# usb_breakout.net
KiCad netlist of a schematic drawn in EAGLE
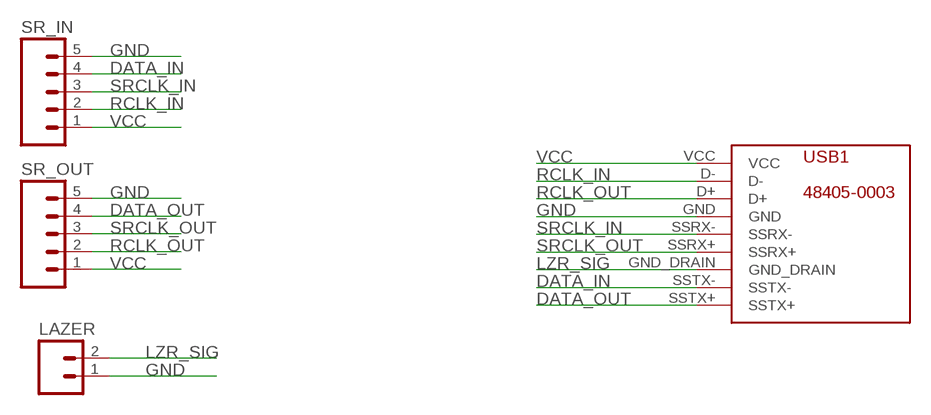
[diagram p0: schematic, sheet 1]

(export (version "E")
  (design (tool "Eeschema 10.0.6"))
  (components
    (comp (ref "LAZER")
      (value "M02PTH")
      (footprint "eagle-import:1X02")
      (libsource (lib "eagle-import") (part "M02PTH"))
    )
    (comp (ref "SR_IN")
      (value "M05PTH")
      (footprint "eagle-import:1X05")
      (libsource (lib "eagle-import") (part "M05PTH"))
    )
    (comp (ref "SR_OUT")
      (value "M05PTH")
      (footprint "eagle-import:1X05")
      (libsource (lib "eagle-import") (part "M05PTH"))
    )
    (comp (ref "USB1")
      (value "48405-0003")
      (footprint "eagle-import:48405-0003MYVERSION")
      (libsource (lib "eagle-import") (part "48405-0003"))
    )
  )
  (nets
    (net (code "1") (name "/DATA_IN") (class "Default")
      (node (ref "SR_IN") (pin "4") (pinfunction "4_4") (pintype "passive"))
      (node (ref "USB1") (pin "SSTX-") (pinfunction "SSTX-_SSTX-") (pintype "bidirectional"))
    )
    (net (code "2") (name "/DATA_OUT") (class "Default")
      (node (ref "SR_OUT") (pin "4") (pinfunction "4_4") (pintype "passive"))
      (node (ref "USB1") (pin "SSTX+") (pinfunction "SSTX+_SSTX+") (pintype "bidirectional"))
    )
    (net (code "3") (name "/GND") (class "Default")
      (node (ref "LAZER") (pin "1") (pinfunction "1_1") (pintype "passive"))
      (node (ref "SR_IN") (pin "5") (pinfunction "5_5") (pintype "passive"))
      (node (ref "SR_OUT") (pin "5") (pinfunction "5_5") (pintype "passive"))
      (node (ref "USB1") (pin "GND") (pinfunction "GND_GND") (pintype "bidirectional"))
    )
    (net (code "4") (name "/LZR_SIG") (class "Default")
      (node (ref "LAZER") (pin "2") (pinfunction "2_2") (pintype "passive"))
      (node (ref "USB1") (pin "GND_DRAIN") (pinfunction "GND_DRAIN_GND_DRAIN") (pintype "bidirectional"))
    )
    (net (code "5") (name "/RCLK_IN") (class "Default")
      (node (ref "SR_IN") (pin "2") (pinfunction "2_2") (pintype "passive"))
      (node (ref "USB1") (pin "D-") (pinfunction "D-_D-") (pintype "bidirectional"))
    )
    (net (code "6") (name "/RCLK_OUT") (class "Default")
      (node (ref "SR_OUT") (pin "2") (pinfunction "2_2") (pintype "passive"))
      (node (ref "USB1") (pin "D+") (pinfunction "D+_D+") (pintype "bidirectional"))
    )
    (net (code "7") (name "/SRCLK_IN") (class "Default")
      (node (ref "SR_IN") (pin "3") (pinfunction "3_3") (pintype "passive"))
      (node (ref "USB1") (pin "SSRX-") (pinfunction "SSRX-_SSRX-") (pintype "bidirectional"))
    )
    (net (code "8") (name "/SRCLK_OUT") (class "Default")
      (node (ref "SR_OUT") (pin "3") (pinfunction "3_3") (pintype "passive"))
      (node (ref "USB1") (pin "SSRX+") (pinfunction "SSRX+_SSRX+") (pintype "bidirectional"))
    )
    (net (code "9") (name "/VCC") (class "Default")
      (node (ref "SR_IN") (pin "1") (pinfunction "1_1") (pintype "passive"))
      (node (ref "SR_OUT") (pin "1") (pinfunction "1_1") (pintype "passive"))
      (node (ref "USB1") (pin "VCC") (pinfunction "VCC_VCC") (pintype "bidirectional"))
    )
  )
)
